# EasyEDA_Pro_IP5355_ABCC_V1_0.net
KiCad netlist of a schematic drawn in EasyEDA Pro
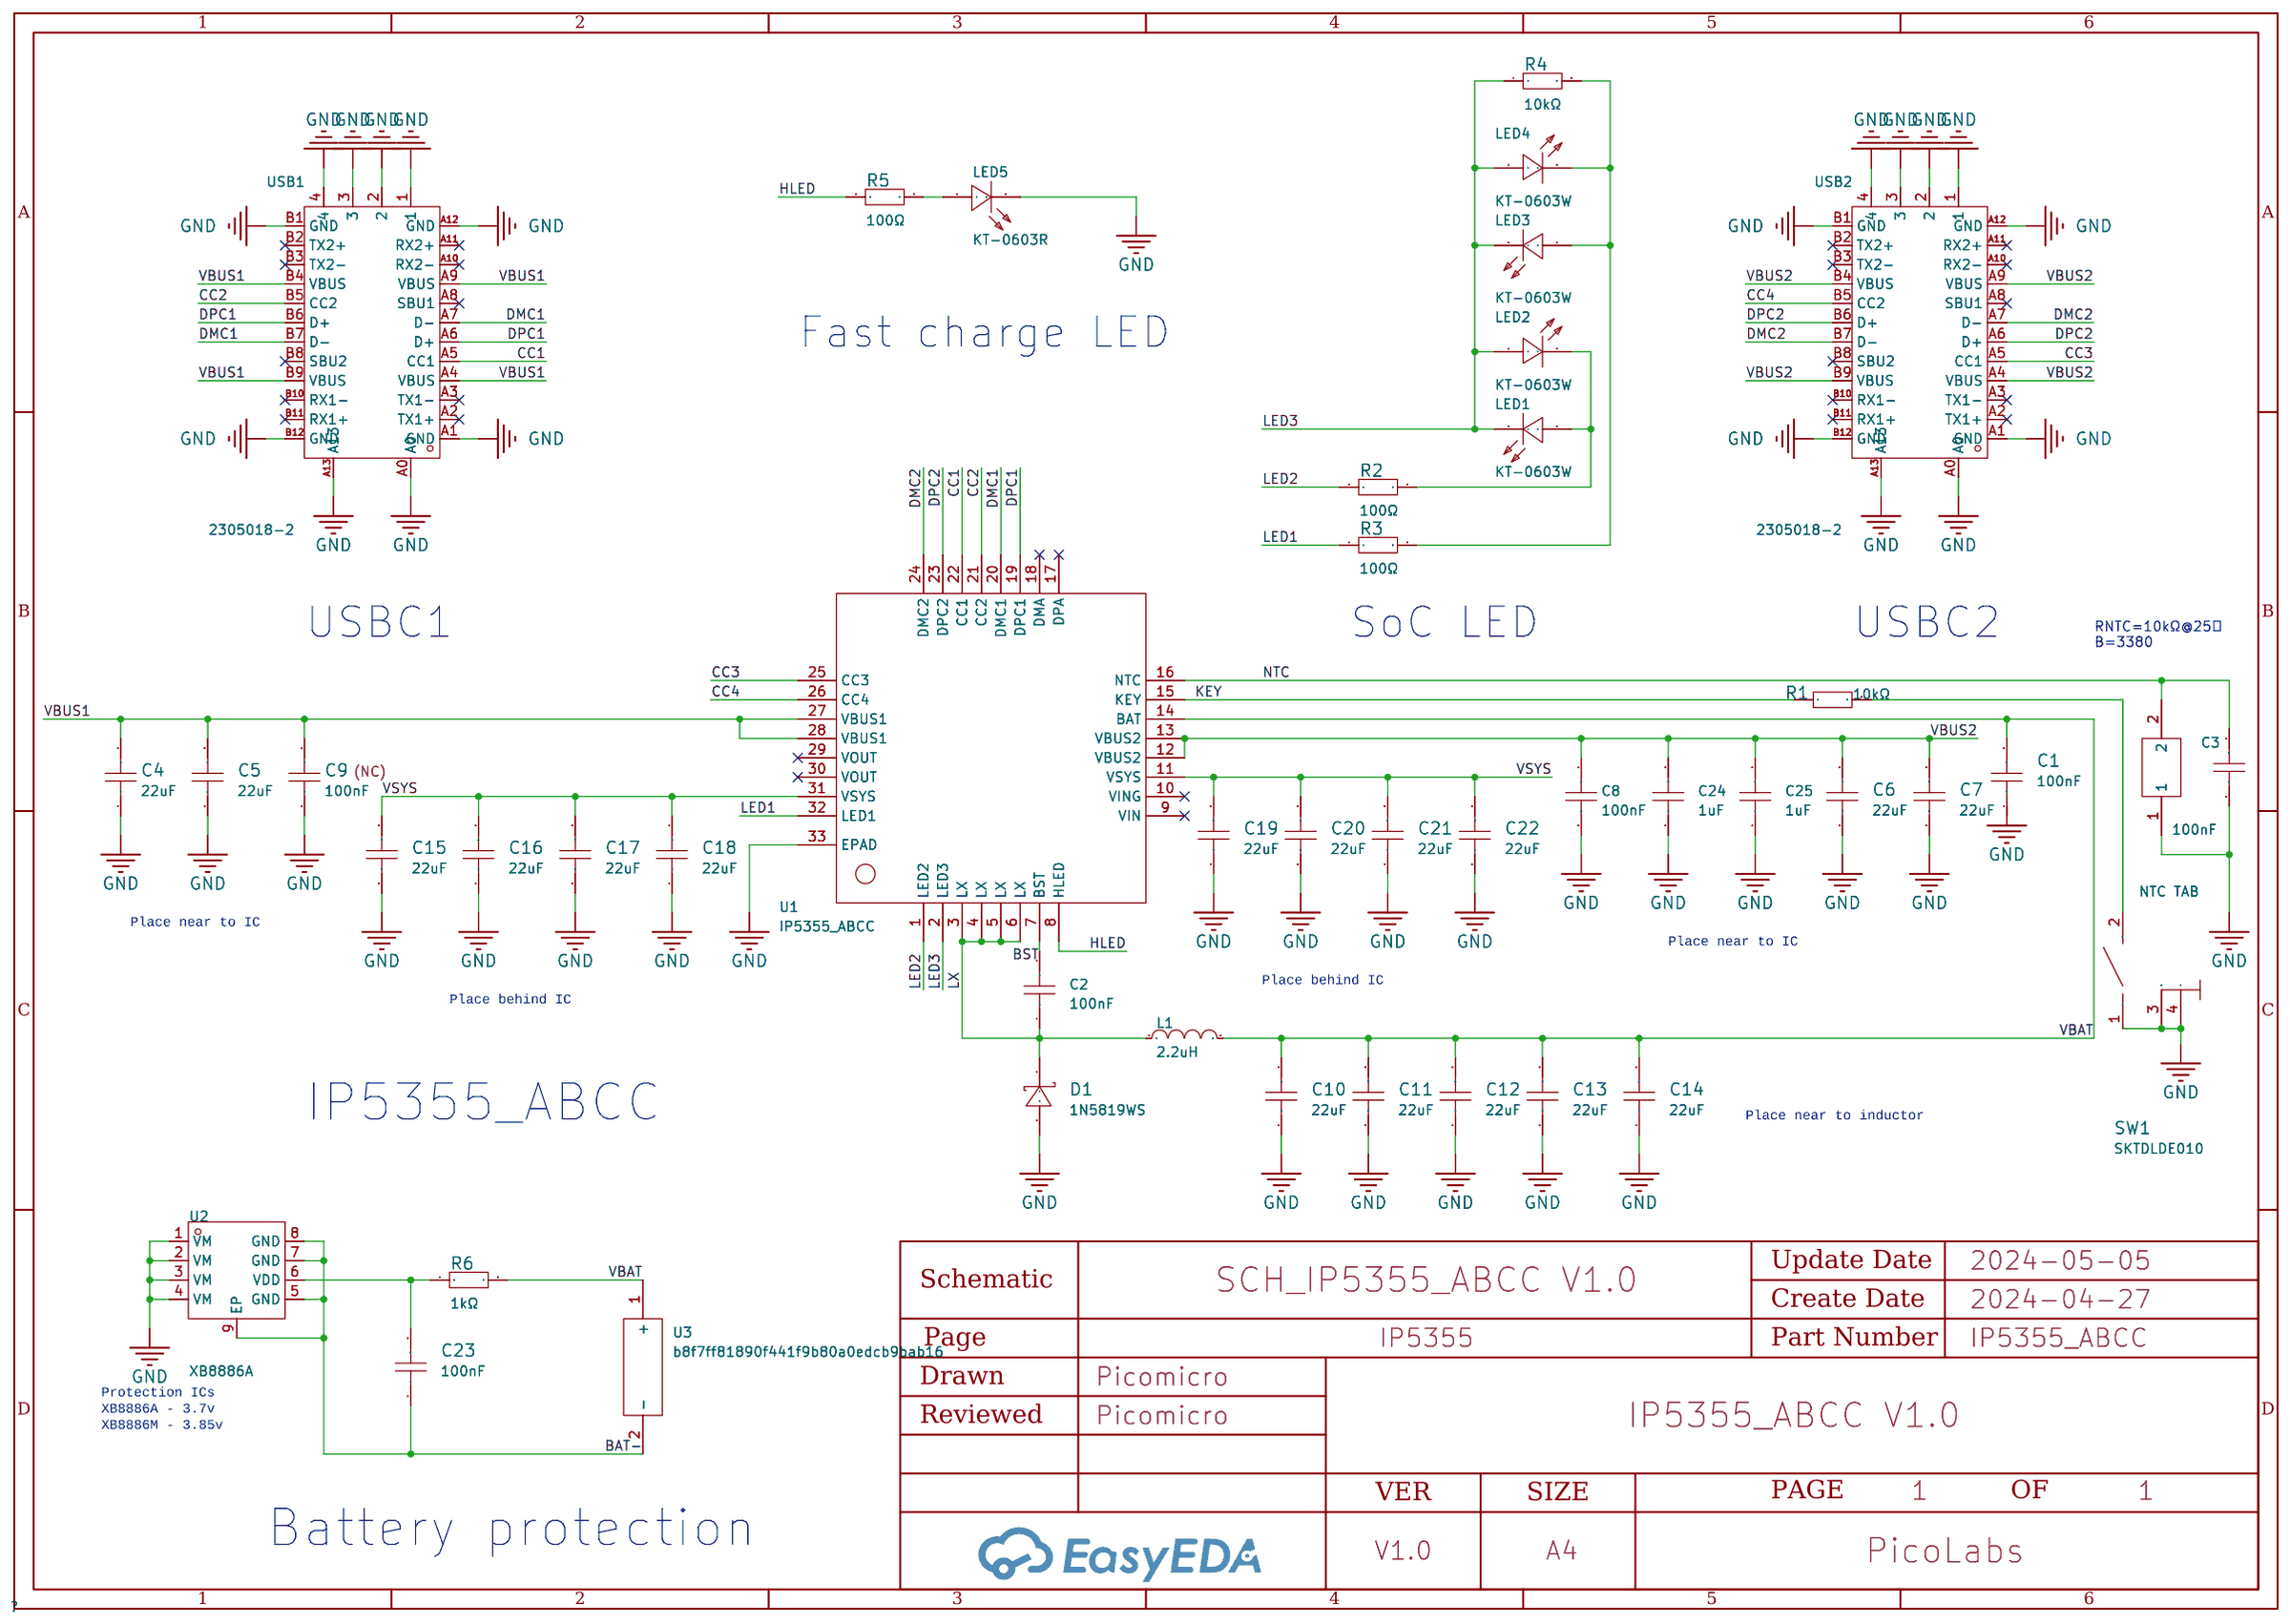
[diagram p0: schematic sheet]

(export (version "E")
  (design (tool "Eeschema 10.0.6"))
  (components
    (comp (ref "C1")
      (value "100nF")
      (footprint "easyedapro:C0603")
      (fields
        (field (name "Manufacturer Part") "CC0603KRX7R9BB104")
        (field (name "Manufacturer") "YAGEO(国巨)")
      )
      (libsource (lib "easyedapro") (part "CC0603KRX7R9BB104"))
    )
    (comp (ref "C2")
      (value "100nF")
      (footprint "easyedapro:C0402")
      (fields
        (field (name "Manufacturer Part") "CL05B104KB54PNC")
        (field (name "Manufacturer") "SAMSUNG(三星)")
      )
      (libsource (lib "easyedapro") (part "CL05B104KB54PNC"))
    )
    (comp (ref "C3")
      (value "100nF")
      (footprint "easyedapro:C0402")
      (fields
        (field (name "Manufacturer Part") "CL05B104KB54PNC")
        (field (name "Manufacturer") "SAMSUNG(三星)")
      )
      (libsource (lib "easyedapro") (part "CL05B104KB54PNC"))
    )
    (comp (ref "C4")
      (value "22uF")
      (footprint "easyedapro:C0805")
      (fields
        (field (name "Manufacturer Part") "CL21A226MAQNNNE")
        (field (name "Manufacturer") "SAMSUNG(三星)")
      )
      (libsource (lib "easyedapro") (part "CL21A226MAQNNNE"))
    )
    (comp (ref "C5")
      (value "22uF")
      (footprint "easyedapro:C0805")
      (fields
        (field (name "Manufacturer Part") "CL21A226MAQNNNE")
        (field (name "Manufacturer") "SAMSUNG(三星)")
      )
      (libsource (lib "easyedapro") (part "CL21A226MAQNNNE"))
    )
    (comp (ref "C6")
      (value "22uF")
      (footprint "easyedapro:C0805")
      (fields
        (field (name "Manufacturer Part") "CL21A226MAQNNNE")
        (field (name "Manufacturer") "SAMSUNG(三星)")
      )
      (libsource (lib "easyedapro") (part "CL21A226MAQNNNE"))
    )
    (comp (ref "C7")
      (value "22uF")
      (footprint "easyedapro:C0805")
      (fields
        (field (name "Manufacturer Part") "CL21A226MAQNNNE")
        (field (name "Manufacturer") "SAMSUNG(三星)")
      )
      (libsource (lib "easyedapro") (part "CL21A226MAQNNNE"))
    )
    (comp (ref "C8")
      (value "100nF")
      (footprint "easyedapro:C0402")
      (fields
        (field (name "Manufacturer Part") "CL05B104KB54PNC")
        (field (name "Manufacturer") "SAMSUNG(三星)")
      )
      (libsource (lib "easyedapro") (part "CL05B104KB54PNC"))
    )
    (comp (ref "C9")
      (value "100nF")
      (footprint "easyedapro:C0402")
      (fields
        (field (name "Manufacturer Part") "CL05B104KB54PNC")
        (field (name "Manufacturer") "SAMSUNG(三星)")
        (field (name "Note") "(NC)")
      )
      (libsource (lib "easyedapro") (part "CL05B104KB54PNC"))
    )
    (comp (ref "C10")
      (value "22uF")
      (footprint "easyedapro:C0805")
      (fields
        (field (name "Manufacturer Part") "CL21A226MAQNNNE")
        (field (name "Manufacturer") "SAMSUNG(三星)")
      )
      (libsource (lib "easyedapro") (part "CL21A226MAQNNNE"))
    )
    (comp (ref "C11")
      (value "22uF")
      (footprint "easyedapro:C0805")
      (fields
        (field (name "Manufacturer Part") "CL21A226MAQNNNE")
        (field (name "Manufacturer") "SAMSUNG(三星)")
      )
      (libsource (lib "easyedapro") (part "CL21A226MAQNNNE"))
    )
    (comp (ref "C12")
      (value "22uF")
      (footprint "easyedapro:C0805")
      (fields
        (field (name "Manufacturer Part") "CL21A226MAQNNNE")
        (field (name "Manufacturer") "SAMSUNG(三星)")
      )
      (libsource (lib "easyedapro") (part "CL21A226MAQNNNE"))
    )
    (comp (ref "C13")
      (value "22uF")
      (footprint "easyedapro:C0805")
      (fields
        (field (name "Manufacturer Part") "CL21A226MAQNNNE")
        (field (name "Manufacturer") "SAMSUNG(三星)")
      )
      (libsource (lib "easyedapro") (part "CL21A226MAQNNNE"))
    )
    (comp (ref "C14")
      (value "22uF")
      (footprint "easyedapro:C0805")
      (fields
        (field (name "Manufacturer Part") "CL21A226MAQNNNE")
        (field (name "Manufacturer") "SAMSUNG(三星)")
      )
      (libsource (lib "easyedapro") (part "CL21A226MAQNNNE"))
    )
    (comp (ref "C15")
      (value "22uF")
      (footprint "easyedapro:C0805")
      (fields
        (field (name "Manufacturer Part") "CL21A226MAQNNNE")
        (field (name "Manufacturer") "SAMSUNG(三星)")
      )
      (libsource (lib "easyedapro") (part "CL21A226MAQNNNE"))
    )
    (comp (ref "C16")
      (value "22uF")
      (footprint "easyedapro:C0805")
      (fields
        (field (name "Manufacturer Part") "CL21A226MAQNNNE")
        (field (name "Manufacturer") "SAMSUNG(三星)")
      )
      (libsource (lib "easyedapro") (part "CL21A226MAQNNNE"))
    )
    (comp (ref "C17")
      (value "22uF")
      (footprint "easyedapro:C0805")
      (fields
        (field (name "Manufacturer Part") "CL21A226MAQNNNE")
        (field (name "Manufacturer") "SAMSUNG(三星)")
      )
      (libsource (lib "easyedapro") (part "CL21A226MAQNNNE"))
    )
    (comp (ref "C18")
      (value "22uF")
      (footprint "easyedapro:C0805")
      (fields
        (field (name "Manufacturer Part") "CL21A226MAQNNNE")
        (field (name "Manufacturer") "SAMSUNG(三星)")
      )
      (libsource (lib "easyedapro") (part "CL21A226MAQNNNE"))
    )
    (comp (ref "C19")
      (value "22uF")
      (footprint "easyedapro:C0805")
      (fields
        (field (name "Manufacturer Part") "CL21A226MAQNNNE")
        (field (name "Manufacturer") "SAMSUNG(三星)")
      )
      (libsource (lib "easyedapro") (part "CL21A226MAQNNNE"))
    )
    (comp (ref "C20")
      (value "22uF")
      (footprint "easyedapro:C0805")
      (fields
        (field (name "Manufacturer Part") "CL21A226MAQNNNE")
        (field (name "Manufacturer") "SAMSUNG(三星)")
      )
      (libsource (lib "easyedapro") (part "CL21A226MAQNNNE"))
    )
    (comp (ref "C21")
      (value "22uF")
      (footprint "easyedapro:C0805")
      (fields
        (field (name "Manufacturer Part") "CL21A226MAQNNNE")
        (field (name "Manufacturer") "SAMSUNG(三星)")
      )
      (libsource (lib "easyedapro") (part "CL21A226MAQNNNE"))
    )
    (comp (ref "C22")
      (value "22uF")
      (footprint "easyedapro:C0805")
      (fields
        (field (name "Manufacturer Part") "CL21A226MAQNNNE")
        (field (name "Manufacturer") "SAMSUNG(三星)")
      )
      (libsource (lib "easyedapro") (part "CL21A226MAQNNNE"))
    )
    (comp (ref "C23")
      (value "100nF")
      (footprint "easyedapro:C0603")
      (fields
        (field (name "Manufacturer Part") "CC0603KRX7R9BB104")
        (field (name "Manufacturer") "YAGEO(国巨)")
      )
      (libsource (lib "easyedapro") (part "CC0603KRX7R9BB104"))
    )
    (comp (ref "C24")
      (value "1uF")
      (footprint "easyedapro:C0402")
      (fields
        (field (name "Manufacturer Part") "CL05A105KA5NQNC")
        (field (name "Manufacturer") "SAMSUNG(三星)")
      )
      (libsource (lib "easyedapro") (part "CL05A105KA5NQNC"))
    )
    (comp (ref "C25")
      (value "1uF")
      (footprint "easyedapro:C0402")
      (fields
        (field (name "Manufacturer Part") "CL05A105KA5NQNC")
        (field (name "Manufacturer") "SAMSUNG(三星)")
      )
      (libsource (lib "easyedapro") (part "CL05A105KA5NQNC"))
    )
    (comp (ref "CON1")
      (value "NTC TAB")
      (footprint "easyedapro:NTC_connector")
      (libsource (lib "easyedapro") (part "NTC_connector"))
    )
    (comp (ref "D1")
      (value "1N5819WS")
      (footprint "easyedapro:SOD-323_L1.8-W1.3-LS2.5-RD")
      (description "Forward Voltage (Vf@If):600mV@1A Reverse Voltage (Vr):40V Average Rectified Current (Io):1A")
      (fields (field (name "Manufacturer") "Hottech(合科泰)"))
      (libsource (lib "easyedapro") (part "1N5819WS"))
    )
    (comp (ref "L1")
      (value "2.2uH")
      (footprint "easyedapro:IND-SMD_L13.5-W12.6_125CDMCC-DS")
      (fields
        (field (name "Manufacturer Part") "125CDMCCDS-2R2MC")
        (field (name "Manufacturer") "Sumida(胜美达)")
      )
      (libsource (lib "easyedapro") (part "125CDMCCDS-2R2MC"))
    )
    (comp (ref "LED1")
      (value "KT-0603W")
      (footprint "easyedapro:LED0603-R-RD_WHITE")
      (description "Emitted Color:White")
      (fields (field (name "Manufacturer") "KENTO"))
      (libsource (lib "easyedapro") (part "0603White light_C2290"))
    )
    (comp (ref "LED2")
      (value "KT-0603W")
      (footprint "easyedapro:LED0603-R-RD_WHITE")
      (description "Emitted Color:White")
      (fields (field (name "Manufacturer") "KENTO"))
      (libsource (lib "easyedapro") (part "0603White light_C2290"))
    )
    (comp (ref "LED3")
      (value "KT-0603W")
      (footprint "easyedapro:LED0603-R-RD_WHITE")
      (description "Emitted Color:White")
      (fields (field (name "Manufacturer") "KENTO"))
      (libsource (lib "easyedapro") (part "0603White light_C2290"))
    )
    (comp (ref "LED4")
      (value "KT-0603W")
      (footprint "easyedapro:LED0603-R-RD_WHITE")
      (description "Emitted Color:White")
      (fields (field (name "Manufacturer") "KENTO"))
      (libsource (lib "easyedapro") (part "0603White light_C2290"))
    )
    (comp (ref "LED5")
      (value "KT-0603R")
      (footprint "easyedapro:LED0603-RD")
      (fields (field (name "Manufacturer") "KENTO"))
      (libsource (lib "easyedapro") (part "KT-0603R"))
    )
    (comp (ref "R1")
      (value "10kΩ")
      (footprint "easyedapro:R0402")
      (fields
        (field (name "Manufacturer Part") "0402WGF1002TCE")
        (field (name "Manufacturer") "UNI-ROYAL(厚声)")
      )
      (libsource (lib "easyedapro") (part "0402WGF1002TCE"))
    )
    (comp (ref "R2")
      (value "100Ω")
      (footprint "easyedapro:R0402")
      (fields
        (field (name "Manufacturer Part") "0402WGF1000TCE")
        (field (name "Manufacturer") "UNI-ROYAL(厚声)")
      )
      (libsource (lib "easyedapro") (part "0402WGF1000TCE"))
    )
    (comp (ref "R3")
      (value "100Ω")
      (footprint "easyedapro:R0402")
      (fields
        (field (name "Manufacturer Part") "0402WGF1000TCE")
        (field (name "Manufacturer") "UNI-ROYAL(厚声)")
      )
      (libsource (lib "easyedapro") (part "0402WGF1000TCE"))
    )
    (comp (ref "R4")
      (value "10kΩ")
      (footprint "easyedapro:R0402")
      (fields
        (field (name "Manufacturer Part") "0402WGF1002TCE")
        (field (name "Manufacturer") "UNI-ROYAL(厚声)")
      )
      (libsource (lib "easyedapro") (part "0402WGF1002TCE"))
    )
    (comp (ref "R5")
      (value "100Ω")
      (footprint "easyedapro:R0402")
      (fields
        (field (name "Manufacturer Part") "0402WGF1000TCE")
        (field (name "Manufacturer") "UNI-ROYAL(厚声)")
      )
      (libsource (lib "easyedapro") (part "0402WGF1000TCE"))
    )
    (comp (ref "R6")
      (value "1kΩ")
      (footprint "easyedapro:R0603")
      (fields
        (field (name "Manufacturer Part") "0603WAF1001T5E")
        (field (name "Manufacturer") "UNI-ROYAL(厚声)")
      )
      (libsource (lib "easyedapro") (part "0603WAF1001T5E"))
    )
    (comp (ref "SW1")
      (value "SKTDLDE010")
      (footprint "easyedapro:KEY-SMD_SKTDLDE010")
      (fields (field (name "Manufacturer") "ALPSALPINE(阿尔卑斯阿尔派)"))
      (libsource (lib "easyedapro") (part "SKTDLDE010"))
    )
    (comp (ref "U1")
      (value "IP5355_ABCC")
      (footprint "easyedapro:QFN-32_L5.0-W5.0-P0.50-TL-EP3.5_IP5355")
      (libsource (lib "easyedapro") (part "IP5355_ABCC"))
    )
    (comp (ref "U2")
      (value "XB8886A")
      (footprint "easyedapro:SOIC-8_L5.0-W4.0-P1.27-LS6.0-BL-EP2.0")
      (fields (field (name "Manufacturer") "xysemi(赛芯微)"))
      (libsource (lib "easyedapro") (part "XB8886A"))
    )
    (comp (ref "U3")
      (value "b8f7ff81890f441f9b80a0edcb9bab16")
      (footprint "easyedapro:9858102 BAT TAB")
      (libsource (lib "easyedapro") (part "9858102 BAT TAB"))
    )
    (comp (ref "USB1")
      (value "2305018-2")
      (footprint "easyedapro:USB-SMD_2305018-2")
      (fields (field (name "Manufacturer") "TE Connectivity(泰科电子)"))
      (libsource (lib "easyedapro") (part "2305018-2"))
    )
    (comp (ref "USB2")
      (value "2305018-2")
      (footprint "easyedapro:USB-SMD_2305018-2")
      (fields (field (name "Manufacturer") "TE Connectivity(泰科电子)"))
      (libsource (lib "easyedapro") (part "2305018-2"))
    )
  )
  (nets
    (net (code "1") (name "/BAT-") (class "Default")
      (node (ref "C23") (pin "1") (pinfunction "1_1") (pintype "input"))
      (node (ref "U2") (pin "5") (pinfunction "GND_5") (pintype "input"))
      (node (ref "U2") (pin "7") (pinfunction "GND_7") (pintype "input"))
      (node (ref "U2") (pin "8") (pinfunction "GND_8") (pintype "input"))
      (node (ref "U2") (pin "9") (pinfunction "EP_9") (pintype "input"))
      (node (ref "U3") (pin "2") (pinfunction "-_2") (pintype "input"))
    )
    (net (code "2") (name "/BST") (class "Default")
      (node (ref "C2") (pin "2") (pinfunction "2_2") (pintype "input"))
      (node (ref "U1") (pin "7") (pinfunction "BST_7") (pintype "input"))
    )
    (net (code "3") (name "/CC1") (class "Default")
      (node (ref "U1") (pin "22") (pinfunction "CC1_22") (pintype "input"))
      (node (ref "USB1") (pin "A5") (pinfunction "CC1_A5") (pintype "unspecified"))
    )
    (net (code "4") (name "/CC2") (class "Default")
      (node (ref "U1") (pin "21") (pinfunction "CC2_21") (pintype "input"))
      (node (ref "USB1") (pin "B5") (pinfunction "CC2_B5") (pintype "unspecified"))
    )
    (net (code "5") (name "/CC3") (class "Default")
      (node (ref "U1") (pin "25") (pinfunction "CC3_25") (pintype "input"))
      (node (ref "USB2") (pin "A5") (pinfunction "CC1_A5") (pintype "unspecified"))
    )
    (net (code "6") (name "/CC4") (class "Default")
      (node (ref "U1") (pin "26") (pinfunction "CC4_26") (pintype "input"))
      (node (ref "USB2") (pin "B5") (pinfunction "CC2_B5") (pintype "unspecified"))
    )
    (net (code "7") (name "/DMC1") (class "Default")
      (node (ref "U1") (pin "20") (pinfunction "DMC1_20") (pintype "input"))
      (node (ref "USB1") (pin "A7") (pinfunction "D-_A7") (pintype "unspecified"))
      (node (ref "USB1") (pin "B7") (pinfunction "D-_B7") (pintype "unspecified"))
    )
    (net (code "8") (name "/DMC2") (class "Default")
      (node (ref "U1") (pin "24") (pinfunction "DMC2_24") (pintype "input"))
      (node (ref "USB2") (pin "A7") (pinfunction "D-_A7") (pintype "unspecified"))
      (node (ref "USB2") (pin "B7") (pinfunction "D-_B7") (pintype "unspecified"))
    )
    (net (code "9") (name "/DPC1") (class "Default")
      (node (ref "U1") (pin "19") (pinfunction "DPC1_19") (pintype "input"))
      (node (ref "USB1") (pin "A6") (pinfunction "D+_A6") (pintype "unspecified"))
      (node (ref "USB1") (pin "B6") (pinfunction "D+_B6") (pintype "unspecified"))
    )
    (net (code "10") (name "/DPC2") (class "Default")
      (node (ref "U1") (pin "23") (pinfunction "DPC2_23") (pintype "input"))
      (node (ref "USB2") (pin "A6") (pinfunction "D+_A6") (pintype "unspecified"))
      (node (ref "USB2") (pin "B6") (pinfunction "D+_B6") (pintype "unspecified"))
    )
    (net (code "11") (name "/HLED") (class "Default")
      (node (ref "R5") (pin "1") (pinfunction "1_1") (pintype "input"))
      (node (ref "U1") (pin "8") (pinfunction "HLED_8") (pintype "input"))
    )
    (net (code "12") (name "/KEY") (class "Default")
      (node (ref "R1") (pin "1") (pinfunction "1_1") (pintype "input"))
      (node (ref "U1") (pin "15") (pinfunction "KEY_15") (pintype "input"))
    )
    (net (code "13") (name "/LED1") (class "Default")
      (node (ref "R3") (pin "1") (pinfunction "1_1") (pintype "input"))
      (node (ref "U1") (pin "32") (pinfunction "LED1_32") (pintype "input"))
    )
    (net (code "14") (name "/LED2") (class "Default")
      (node (ref "R2") (pin "1") (pinfunction "1_1") (pintype "input"))
      (node (ref "U1") (pin "1") (pinfunction "LED2_1") (pintype "input"))
    )
    (net (code "15") (name "/LED3") (class "Default")
      (node (ref "LED1") (pin "2") (pinfunction "K_2") (pintype "unspecified"))
      (node (ref "LED2") (pin "1") (pinfunction "A_1") (pintype "unspecified"))
      (node (ref "LED3") (pin "2") (pinfunction "K_2") (pintype "unspecified"))
      (node (ref "LED4") (pin "1") (pinfunction "A_1") (pintype "unspecified"))
      (node (ref "R4") (pin "1") (pinfunction "1_1") (pintype "input"))
      (node (ref "U1") (pin "2") (pinfunction "LED3_2") (pintype "input"))
    )
    (net (code "16") (name "/LX") (class "Default")
      (node (ref "C2") (pin "1") (pinfunction "1_1") (pintype "input"))
      (node (ref "D1") (pin "1") (pinfunction "K_1") (pintype "input"))
      (node (ref "L1") (pin "1") (pinfunction "1_1") (pintype "input"))
      (node (ref "U1") (pin "3") (pinfunction "LX_3") (pintype "input"))
      (node (ref "U1") (pin "4") (pinfunction "LX_4") (pintype "input"))
      (node (ref "U1") (pin "5") (pinfunction "LX_5") (pintype "input"))
      (node (ref "U1") (pin "6") (pinfunction "LX_6") (pintype "input"))
    )
    (net (code "17") (name "/NTC") (class "Default")
      (node (ref "C3") (pin "1") (pinfunction "1_1") (pintype "input"))
      (node (ref "CON1") (pin "2") (pinfunction "2_2") (pintype "input"))
      (node (ref "U1") (pin "16") (pinfunction "NTC_16") (pintype "input"))
    )
    (net (code "18") (name "/VBAT") (class "Default")
      (node (ref "C1") (pin "2") (pinfunction "2_2") (pintype "input"))
      (node (ref "C10") (pin "2") (pinfunction "2_2") (pintype "input"))
      (node (ref "C11") (pin "2") (pinfunction "2_2") (pintype "input"))
      (node (ref "C12") (pin "2") (pinfunction "2_2") (pintype "input"))
      (node (ref "C13") (pin "2") (pinfunction "2_2") (pintype "input"))
      (node (ref "C14") (pin "2") (pinfunction "2_2") (pintype "input"))
      (node (ref "L1") (pin "2") (pinfunction "2_2") (pintype "input"))
      (node (ref "R6") (pin "2") (pinfunction "2_2") (pintype "input"))
      (node (ref "U1") (pin "14") (pinfunction "BAT_14") (pintype "input"))
      (node (ref "U3") (pin "1") (pinfunction "+_1") (pintype "input"))
    )
    (net (code "19") (name "/VBUS1") (class "Default")
      (node (ref "C4") (pin "2") (pinfunction "2_2") (pintype "input"))
      (node (ref "C5") (pin "2") (pinfunction "2_2") (pintype "input"))
      (node (ref "C9") (pin "1") (pinfunction "1_1") (pintype "input"))
      (node (ref "U1") (pin "27") (pinfunction "VBUS1_27") (pintype "input"))
      (node (ref "U1") (pin "28") (pinfunction "VBUS1_28") (pintype "input"))
      (node (ref "USB1") (pin "A4") (pinfunction "VBUS_A4") (pintype "unspecified"))
      (node (ref "USB1") (pin "A9") (pinfunction "VBUS_A9") (pintype "unspecified"))
      (node (ref "USB1") (pin "B4") (pinfunction "VBUS_B4") (pintype "unspecified"))
      (node (ref "USB1") (pin "B9") (pinfunction "VBUS_B9") (pintype "unspecified"))
    )
    (net (code "20") (name "/VBUS2") (class "Default")
      (node (ref "C24") (pin "2") (pinfunction "2_2") (pintype "unspecified"))
      (node (ref "C25") (pin "2") (pinfunction "2_2") (pintype "unspecified"))
      (node (ref "C6") (pin "2") (pinfunction "2_2") (pintype "input"))
      (node (ref "C7") (pin "2") (pinfunction "2_2") (pintype "input"))
      (node (ref "C8") (pin "1") (pinfunction "1_1") (pintype "input"))
      (node (ref "U1") (pin "12") (pinfunction "VBUS2_12") (pintype "input"))
      (node (ref "U1") (pin "13") (pinfunction "VBUS2_13") (pintype "input"))
      (node (ref "USB2") (pin "A4") (pinfunction "VBUS_A4") (pintype "unspecified"))
      (node (ref "USB2") (pin "A9") (pinfunction "VBUS_A9") (pintype "unspecified"))
      (node (ref "USB2") (pin "B4") (pinfunction "VBUS_B4") (pintype "unspecified"))
      (node (ref "USB2") (pin "B9") (pinfunction "VBUS_B9") (pintype "unspecified"))
    )
    (net (code "21") (name "/VSYS") (class "Default")
      (node (ref "C15") (pin "2") (pinfunction "2_2") (pintype "input"))
      (node (ref "C16") (pin "2") (pinfunction "2_2") (pintype "input"))
      (node (ref "C17") (pin "2") (pinfunction "2_2") (pintype "input"))
      (node (ref "C18") (pin "2") (pinfunction "2_2") (pintype "input"))
      (node (ref "C19") (pin "2") (pinfunction "2_2") (pintype "input"))
      (node (ref "C20") (pin "2") (pinfunction "2_2") (pintype "input"))
      (node (ref "C21") (pin "2") (pinfunction "2_2") (pintype "input"))
      (node (ref "C22") (pin "2") (pinfunction "2_2") (pintype "input"))
      (node (ref "U1") (pin "11") (pinfunction "VSYS_11") (pintype "input"))
      (node (ref "U1") (pin "31") (pinfunction "VSYS_31") (pintype "input"))
    )
    (net (code "22") (name "GND") (class "Default")
      (node (ref "C1") (pin "1") (pinfunction "1_1") (pintype "input"))
      (node (ref "C10") (pin "1") (pinfunction "1_1") (pintype "input"))
      (node (ref "C11") (pin "1") (pinfunction "1_1") (pintype "input"))
      (node (ref "C12") (pin "1") (pinfunction "1_1") (pintype "input"))
      (node (ref "C13") (pin "1") (pinfunction "1_1") (pintype "input"))
      (node (ref "C14") (pin "1") (pinfunction "1_1") (pintype "input"))
      (node (ref "C15") (pin "1") (pinfunction "1_1") (pintype "input"))
      (node (ref "C16") (pin "1") (pinfunction "1_1") (pintype "input"))
      (node (ref "C17") (pin "1") (pinfunction "1_1") (pintype "input"))
      (node (ref "C18") (pin "1") (pinfunction "1_1") (pintype "input"))
      (node (ref "C19") (pin "1") (pinfunction "1_1") (pintype "input"))
      (node (ref "C20") (pin "1") (pinfunction "1_1") (pintype "input"))
      (node (ref "C21") (pin "1") (pinfunction "1_1") (pintype "input"))
      (node (ref "C22") (pin "1") (pinfunction "1_1") (pintype "input"))
      (node (ref "C24") (pin "1") (pinfunction "1_1") (pintype "unspecified"))
      (node (ref "C25") (pin "1") (pinfunction "1_1") (pintype "unspecified"))
      (node (ref "C3") (pin "2") (pinfunction "2_2") (pintype "input"))
      (node (ref "C4") (pin "1") (pinfunction "1_1") (pintype "input"))
      (node (ref "C5") (pin "1") (pinfunction "1_1") (pintype "input"))
      (node (ref "C6") (pin "1") (pinfunction "1_1") (pintype "input"))
      (node (ref "C7") (pin "1") (pinfunction "1_1") (pintype "input"))
      (node (ref "C8") (pin "2") (pinfunction "2_2") (pintype "input"))
      (node (ref "C9") (pin "2") (pinfunction "2_2") (pintype "input"))
      (node (ref "CON1") (pin "1") (pinfunction "1_1") (pintype "input"))
      (node (ref "D1") (pin "2") (pinfunction "A_2") (pintype "input"))
      (node (ref "LED5") (pin "1") (pinfunction "K_1") (pintype "input"))
      (node (ref "SW1") (pin "1") (pinfunction "1_1") (pintype "input"))
      (node (ref "SW1") (pin "3") (pinfunction "3_3") (pintype "input"))
      (node (ref "SW1") (pin "4") (pinfunction "4_4") (pintype "input"))
      (node (ref "U1") (pin "33") (pinfunction "EPAD_33") (pintype "input"))
      (node (ref "U2") (pin "1") (pinfunction "VM_1") (pintype "input"))
      (node (ref "U2") (pin "2") (pinfunction "VM_2") (pintype "input"))
      (node (ref "U2") (pin "3") (pinfunction "VM_3") (pintype "input"))
      (node (ref "U2") (pin "4") (pinfunction "VM_4") (pintype "input"))
      (node (ref "USB1") (pin "1") (pinfunction "1_1") (pintype "unspecified"))
      (node (ref "USB1") (pin "2") (pinfunction "2_2") (pintype "unspecified"))
      (node (ref "USB1") (pin "3") (pinfunction "3_3") (pintype "unspecified"))
      (node (ref "USB1") (pin "4") (pinfunction "4_4") (pintype "unspecified"))
      (node (ref "USB1") (pin "A0") (pinfunction "A0_A0") (pintype "unspecified"))
      (node (ref "USB1") (pin "A1") (pinfunction "GND_A1") (pintype "unspecified"))
      (node (ref "USB1") (pin "A12") (pinfunction "GND_A12") (pintype "unspecified"))
      (node (ref "USB1") (pin "A13") (pinfunction "A13_A13") (pintype "unspecified"))
      (node (ref "USB1") (pin "B1") (pinfunction "GND_B1") (pintype "unspecified"))
      (node (ref "USB1") (pin "B12") (pinfunction "GND_B12") (pintype "unspecified"))
      (node (ref "USB2") (pin "1") (pinfunction "1_1") (pintype "unspecified"))
      (node (ref "USB2") (pin "2") (pinfunction "2_2") (pintype "unspecified"))
      (node (ref "USB2") (pin "3") (pinfunction "3_3") (pintype "unspecified"))
      (node (ref "USB2") (pin "4") (pinfunction "4_4") (pintype "unspecified"))
      (node (ref "USB2") (pin "A0") (pinfunction "A0_A0") (pintype "unspecified"))
      (node (ref "USB2") (pin "A1") (pinfunction "GND_A1") (pintype "unspecified"))
      (node (ref "USB2") (pin "A12") (pinfunction "GND_A12") (pintype "unspecified"))
      (node (ref "USB2") (pin "A13") (pinfunction "A13_A13") (pintype "unspecified"))
      (node (ref "USB2") (pin "B1") (pinfunction "GND_B1") (pintype "unspecified"))
      (node (ref "USB2") (pin "B12") (pinfunction "GND_B12") (pintype "unspecified"))
    )
    (net (code "23") (name "Net-(LED1-A)") (class "Default")
      (node (ref "LED1") (pin "1") (pinfunction "A_1") (pintype "unspecified"))
      (node (ref "LED2") (pin "2") (pinfunction "K_2") (pintype "unspecified"))
      (node (ref "R2") (pin "2") (pinfunction "2_2") (pintype "input"))
    )
    (net (code "24") (name "Net-(LED3-A)") (class "Default")
      (node (ref "LED3") (pin "1") (pinfunction "A_1") (pintype "unspecified"))
      (node (ref "LED4") (pin "2") (pinfunction "K_2") (pintype "unspecified"))
      (node (ref "R3") (pin "2") (pinfunction "2_2") (pintype "input"))
      (node (ref "R4") (pin "2") (pinfunction "2_2") (pintype "input"))
    )
    (net (code "25") (name "Net-(LED5-A)") (class "Default")
      (node (ref "LED5") (pin "2") (pinfunction "A_2") (pintype "input"))
      (node (ref "R5") (pin "2") (pinfunction "2_2") (pintype "input"))
    )
    (net (code "26") (name "Net-(R1-Pad2)") (class "Default")
      (node (ref "R1") (pin "2") (pinfunction "2_2") (pintype "input"))
      (node (ref "SW1") (pin "2") (pinfunction "2_2") (pintype "input"))
    )
    (net (code "27") (name "Net-(U2-VDD)") (class "Default")
      (node (ref "C23") (pin "2") (pinfunction "2_2") (pintype "input"))
      (node (ref "R6") (pin "1") (pinfunction "1_1") (pintype "input"))
      (node (ref "U2") (pin "6") (pinfunction "VDD_6") (pintype "input"))
    )
    (net (code "28") (name "unconnected-(U1-DMA-Pad18)") (class "Default")
      (node (ref "U1") (pin "18") (pinfunction "DMA_18") (pintype "input+no_connect"))
    )
    (net (code "29") (name "unconnected-(U1-DPA-Pad17)") (class "Default")
      (node (ref "U1") (pin "17") (pinfunction "DPA_17") (pintype "input+no_connect"))
    )
    (net (code "30") (name "unconnected-(U1-VIN-Pad9)") (class "Default")
      (node (ref "U1") (pin "9") (pinfunction "VIN_9") (pintype "input+no_connect"))
    )
    (net (code "31") (name "unconnected-(U1-VING-Pad10)") (class "Default")
      (node (ref "U1") (pin "10") (pinfunction "VING_10") (pintype "input+no_connect"))
    )
    (net (code "32") (name "unconnected-(U1-VOUT-Pad29)") (class "Default")
      (node (ref "U1") (pin "29") (pinfunction "VOUT_29") (pintype "input+no_connect"))
    )
    (net (code "33") (name "unconnected-(U1-VOUT-Pad30)") (class "Default")
      (node (ref "U1") (pin "30") (pinfunction "VOUT_30") (pintype "input+no_connect"))
    )
    (net (code "34") (name "unconnected-(USB1-RX1+-PadB11)") (class "Default")
      (node (ref "USB1") (pin "B11") (pinfunction "RX1+_B11") (pintype "unspecified+no_connect"))
    )
    (net (code "35") (name "unconnected-(USB1-RX1--PadB10)") (class "Default")
      (node (ref "USB1") (pin "B10") (pinfunction "RX1-_B10") (pintype "unspecified+no_connect"))
    )
    (net (code "36") (name "unconnected-(USB1-RX2+-PadA11)") (class "Default")
      (node (ref "USB1") (pin "A11") (pinfunction "RX2+_A11") (pintype "unspecified+no_connect"))
    )
    (net (code "37") (name "unconnected-(USB1-RX2--PadA10)") (class "Default")
      (node (ref "USB1") (pin "A10") (pinfunction "RX2-_A10") (pintype "unspecified+no_connect"))
    )
    (net (code "38") (name "unconnected-(USB1-SBU1-PadA8)") (class "Default")
      (node (ref "USB1") (pin "A8") (pinfunction "SBU1_A8") (pintype "unspecified+no_connect"))
    )
    (net (code "39") (name "unconnected-(USB1-SBU2-PadB8)") (class "Default")
      (node (ref "USB1") (pin "B8") (pinfunction "SBU2_B8") (pintype "unspecified+no_connect"))
    )
    (net (code "40") (name "unconnected-(USB1-TX1+-PadA2)") (class "Default")
      (node (ref "USB1") (pin "A2") (pinfunction "TX1+_A2") (pintype "unspecified+no_connect"))
    )
    (net (code "41") (name "unconnected-(USB1-TX1--PadA3)") (class "Default")
      (node (ref "USB1") (pin "A3") (pinfunction "TX1-_A3") (pintype "unspecified+no_connect"))
    )
    (net (code "42") (name "unconnected-(USB1-TX2+-PadB2)") (class "Default")
      (node (ref "USB1") (pin "B2") (pinfunction "TX2+_B2") (pintype "unspecified+no_connect"))
    )
    (net (code "43") (name "unconnected-(USB1-TX2--PadB3)") (class "Default")
      (node (ref "USB1") (pin "B3") (pinfunction "TX2-_B3") (pintype "unspecified+no_connect"))
    )
    (net (code "44") (name "unconnected-(USB2-RX1+-PadB11)") (class "Default")
      (node (ref "USB2") (pin "B11") (pinfunction "RX1+_B11") (pintype "unspecified+no_connect"))
    )
    (net (code "45") (name "unconnected-(USB2-RX1--PadB10)") (class "Default")
      (node (ref "USB2") (pin "B10") (pinfunction "RX1-_B10") (pintype "unspecified+no_connect"))
    )
    (net (code "46") (name "unconnected-(USB2-RX2+-PadA11)") (class "Default")
      (node (ref "USB2") (pin "A11") (pinfunction "RX2+_A11") (pintype "unspecified+no_connect"))
    )
    (net (code "47") (name "unconnected-(USB2-RX2--PadA10)") (class "Default")
      (node (ref "USB2") (pin "A10") (pinfunction "RX2-_A10") (pintype "unspecified+no_connect"))
    )
    (net (code "48") (name "unconnected-(USB2-SBU1-PadA8)") (class "Default")
      (node (ref "USB2") (pin "A8") (pinfunction "SBU1_A8") (pintype "unspecified+no_connect"))
    )
    (net (code "49") (name "unconnected-(USB2-SBU2-PadB8)") (class "Default")
      (node (ref "USB2") (pin "B8") (pinfunction "SBU2_B8") (pintype "unspecified+no_connect"))
    )
    (net (code "50") (name "unconnected-(USB2-TX1+-PadA2)") (class "Default")
      (node (ref "USB2") (pin "A2") (pinfunction "TX1+_A2") (pintype "unspecified+no_connect"))
    )
    (net (code "51") (name "unconnected-(USB2-TX1--PadA3)") (class "Default")
      (node (ref "USB2") (pin "A3") (pinfunction "TX1-_A3") (pintype "unspecified+no_connect"))
    )
    (net (code "52") (name "unconnected-(USB2-TX2+-PadB2)") (class "Default")
      (node (ref "USB2") (pin "B2") (pinfunction "TX2+_B2") (pintype "unspecified+no_connect"))
    )
    (net (code "53") (name "unconnected-(USB2-TX2--PadB3)") (class "Default")
      (node (ref "USB2") (pin "B3") (pinfunction "TX2-_B3") (pintype "unspecified+no_connect"))
    )
  )
)
